# ver060_SignalAnalog.net
KiCad netlist of a schematic drawn in Altium Designer
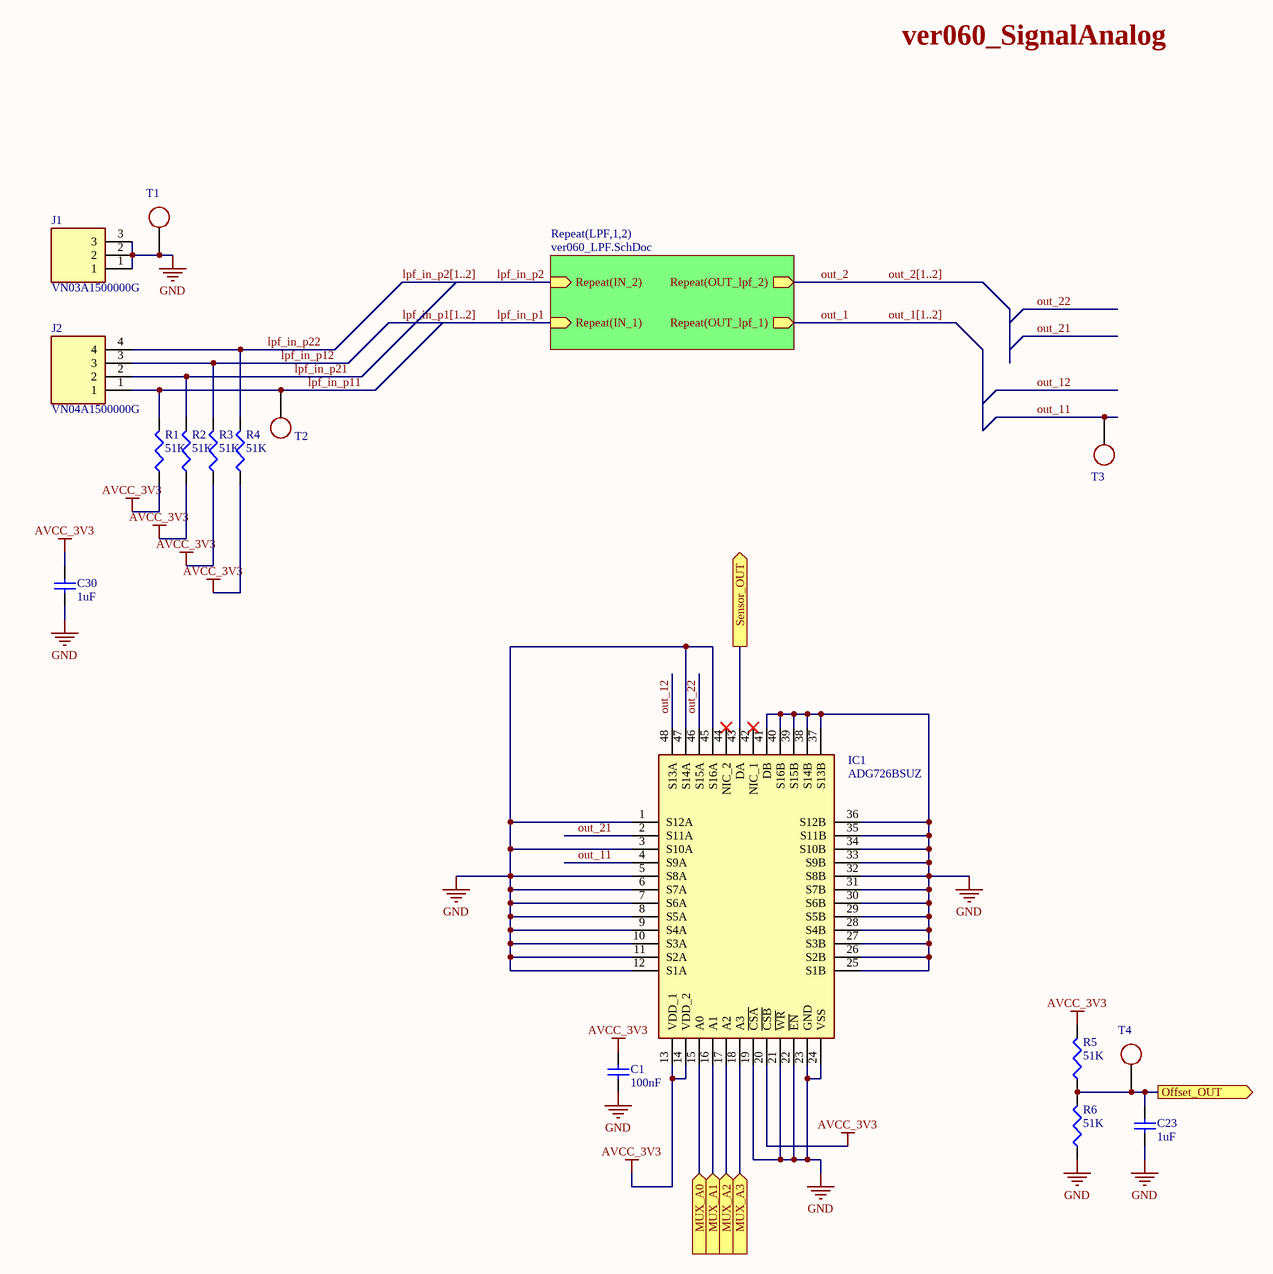
[diagram p0: ver060_SignalAnalog.SchDoc]

(export (version "E")
  (design (tool "Eeschema 10.0.6"))
  (components
    (comp (ref "C1")
      (value "100nF")
      (footprint "1608[0603]")
      (description "Capacitor (Semiconductor SIM Model)")
      (fields (field (name "Comment") "Cap Semi") (field (name "PUBLISHER") "Altium Limited"))
      (libsource (lib "Miscellaneous Devices") (part "Cap Semi"))
    )
    (comp (ref "C23")
      (value "1uF")
      (footprint "1608[0603]")
      (description "Capacitor (Semiconductor SIM Model)")
      (fields (field (name "Comment") "Cap Semi") (field (name "PUBLISHER") "Altium Limited"))
      (libsource (lib "Miscellaneous Devices") (part "Cap Semi"))
    )
    (comp (ref "C30")
      (value "1uF")
      (footprint "1608[0603]")
      (description "Capacitor (Semiconductor SIM Model)")
      (fields (field (name "Comment") "Cap Semi") (field (name "PUBLISHER") "Altium Limited"))
      (libsource (lib "Miscellaneous Devices") (part "Cap Semi"))
    )
    (comp (ref "IC1")
      (value "ADG726BSUZ")
      (footprint "nanowire:QFP50P900X900X120-48N")
      (description "Integrated Circuit")
      (fields (field (name "MOUSER PART NUMBER") "584-ADG726BSUZ"))
      (libsource (lib "*") (part "ADG726BSUZ"))
    )
    (comp (ref "J1")
      (value "VN03A1500000G")
      (footprint "nanowire:VN03A1500000G")
      (description "Connector")
      (fields (field (name "MOUSER PART NUMBER") "649-VN03A15000J0G"))
      (libsource (lib "*") (part "VN03A1500000G"))
    )
    (comp (ref "J2")
      (value "VN04A1500000G")
      (footprint "nanowire:VN04A1500000G")
      (description "Connector")
      (fields (field (name "MOUSER PART NUMBER") "649-VN04A15000J0G"))
      (libsource (lib "*") (part "VN04A1500000G"))
    )
    (comp (ref "R1")
      (value "51K")
      (footprint "J1-0603")
      (description "Resistor")
      (fields (field (name "Comment") "Res3") (field (name "PUBLISHER") "Altium Limited"))
      (libsource (lib "Miscellaneous Devices") (part "Res3"))
    )
    (comp (ref "R2")
      (value "51K")
      (footprint "J1-0603")
      (description "Resistor")
      (fields (field (name "Comment") "Res3") (field (name "PUBLISHER") "Altium Limited"))
      (libsource (lib "Miscellaneous Devices") (part "Res3"))
    )
    (comp (ref "R3")
      (value "51K")
      (footprint "J1-0603")
      (description "Resistor")
      (fields (field (name "Comment") "Res3") (field (name "PUBLISHER") "Altium Limited"))
      (libsource (lib "Miscellaneous Devices") (part "Res3"))
    )
    (comp (ref "R4")
      (value "51K")
      (footprint "J1-0603")
      (description "Resistor")
      (fields (field (name "Comment") "Res3") (field (name "PUBLISHER") "Altium Limited"))
      (libsource (lib "Miscellaneous Devices") (part "Res3"))
    )
    (comp (ref "R5")
      (value "51K")
      (footprint "J1-0603")
      (description "Resistor")
      (fields (field (name "Comment") "Res3") (field (name "PUBLISHER") "Altium Limited"))
      (libsource (lib "Miscellaneous Devices") (part "Res3"))
    )
    (comp (ref "R6")
      (value "51K")
      (footprint "J1-0603")
      (description "Resistor")
      (fields (field (name "Comment") "Res3") (field (name "PUBLISHER") "Altium Limited"))
      (libsource (lib "Miscellaneous Devices") (part "Res3"))
    )
    (comp (ref "T1")
      (value "TP_SMT")
      (footprint "TP_SMT_Round_0.6x0.6")
      (libsource (lib "nanowire") (part "TP_SMT"))
    )
    (comp (ref "T2")
      (value "TP_SMT")
      (footprint "TP_SMT_Round_0.6x0.6")
      (libsource (lib "nanowire") (part "TP_SMT"))
    )
    (comp (ref "T3")
      (value "TP_SMT")
      (footprint "TP_SMT_Round_0.6x0.6")
      (libsource (lib "nanowire") (part "TP_SMT"))
    )
    (comp (ref "T4")
      (value "TP_SMT")
      (footprint "TP_SMT_Round_0.6x0.6")
      (libsource (lib "nanowire") (part "TP_SMT"))
    )
  )
  (nets
    (net (code "1") (name "/MUX_A0") (class "Default")
      (node (ref "IC1") (pin "15") (pinfunction "A0_15") (pintype "passive"))
    )
    (net (code "2") (name "/MUX_A1") (class "Default")
      (node (ref "IC1") (pin "16") (pinfunction "A1_16") (pintype "passive"))
    )
    (net (code "3") (name "/MUX_A2") (class "Default")
      (node (ref "IC1") (pin "17") (pinfunction "A2_17") (pintype "passive"))
    )
    (net (code "4") (name "/MUX_A3") (class "Default")
      (node (ref "IC1") (pin "18") (pinfunction "A3_18") (pintype "passive"))
    )
    (net (code "5") (name "/Offset_OUT") (class "Default")
      (node (ref "C23") (pin "2") (pinfunction "2_2") (pintype "passive"))
      (node (ref "R5") (pin "1") (pinfunction "1_1") (pintype "passive"))
      (node (ref "R6") (pin "2") (pinfunction "2_2") (pintype "passive"))
      (node (ref "T4") (pin "1") (pinfunction "1_1") (pintype "passive"))
    )
    (net (code "6") (name "/Sensor_OUT") (class "Default")
      (node (ref "IC1") (pin "43") (pinfunction "DA_43") (pintype "passive"))
    )
    (net (code "11") (name "/lpf_in_p11") (class "Default")
      (node (ref "J2") (pin "1") (pinfunction "1_1") (pintype "passive"))
      (node (ref "R1") (pin "2") (pinfunction "2_2") (pintype "passive"))
      (node (ref "T2") (pin "1") (pinfunction "1_1") (pintype "passive"))
    )
    (net (code "12") (name "/lpf_in_p12") (class "Default")
      (node (ref "J2") (pin "3") (pinfunction "3_3") (pintype "passive"))
      (node (ref "R3") (pin "2") (pinfunction "2_2") (pintype "passive"))
    )
    (net (code "13") (name "/lpf_in_p21") (class "Default")
      (node (ref "J2") (pin "2") (pinfunction "2_2") (pintype "passive"))
      (node (ref "R2") (pin "2") (pinfunction "2_2") (pintype "passive"))
    )
    (net (code "14") (name "/lpf_in_p22") (class "Default")
      (node (ref "J2") (pin "4") (pinfunction "4_4") (pintype "passive"))
      (node (ref "R4") (pin "2") (pinfunction "2_2") (pintype "passive"))
    )
    (net (code "19") (name "/out_11") (class "Default")
      (node (ref "IC1") (pin "4") (pinfunction "S9A_4") (pintype "passive"))
      (node (ref "T3") (pin "1") (pinfunction "1_1") (pintype "passive"))
    )
    (net (code "20") (name "/out_12") (class "Default")
      (node (ref "IC1") (pin "48") (pinfunction "S13A_48") (pintype "passive"))
    )
    (net (code "21") (name "/out_21") (class "Default")
      (node (ref "IC1") (pin "2") (pinfunction "S11A_2") (pintype "passive"))
    )
    (net (code "22") (name "/out_22") (class "Default")
      (node (ref "IC1") (pin "46") (pinfunction "S15A_46") (pintype "passive"))
    )
    (net (code "23") (name "AVCC_3V3") (class "Default")
      (node (ref "C1") (pin "2") (pinfunction "2_2") (pintype "passive"))
      (node (ref "C30") (pin "2") (pinfunction "2_2") (pintype "passive"))
      (node (ref "IC1") (pin "13") (pinfunction "VDD_1_13") (pintype "passive"))
      (node (ref "IC1") (pin "14") (pinfunction "VDD_2_14") (pintype "passive"))
      (node (ref "IC1") (pin "20") (pinfunction "~{CSB}_20") (pintype "passive"))
      (node (ref "R1") (pin "1") (pinfunction "1_1") (pintype "passive"))
      (node (ref "R2") (pin "1") (pinfunction "1_1") (pintype "passive"))
      (node (ref "R3") (pin "1") (pinfunction "1_1") (pintype "passive"))
      (node (ref "R4") (pin "1") (pinfunction "1_1") (pintype "passive"))
      (node (ref "R5") (pin "2") (pinfunction "2_2") (pintype "passive"))
    )
    (net (code "24") (name "GND") (class "Default")
      (node (ref "C1") (pin "1") (pinfunction "1_1") (pintype "passive"))
      (node (ref "C23") (pin "1") (pinfunction "1_1") (pintype "passive"))
      (node (ref "C30") (pin "1") (pinfunction "1_1") (pintype "passive"))
      (node (ref "IC1") (pin "1") (pinfunction "S12A_1") (pintype "passive"))
      (node (ref "IC1") (pin "10") (pinfunction "S3A_10") (pintype "passive"))
      (node (ref "IC1") (pin "11") (pinfunction "S2A_11") (pintype "passive"))
      (node (ref "IC1") (pin "12") (pinfunction "S1A_12") (pintype "passive"))
      (node (ref "IC1") (pin "19") (pinfunction "~{CSA}_19") (pintype "passive"))
      (node (ref "IC1") (pin "21") (pinfunction "~{WR}_21") (pintype "passive"))
      (node (ref "IC1") (pin "22") (pinfunction "~{EN}_22") (pintype "passive"))
      (node (ref "IC1") (pin "23") (pinfunction "GND_23") (pintype "passive"))
      (node (ref "IC1") (pin "24") (pinfunction "VSS_24") (pintype "passive"))
      (node (ref "IC1") (pin "25") (pinfunction "S1B_25") (pintype "passive"))
      (node (ref "IC1") (pin "26") (pinfunction "S2B_26") (pintype "passive"))
      (node (ref "IC1") (pin "27") (pinfunction "S3B_27") (pintype "passive"))
      (node (ref "IC1") (pin "28") (pinfunction "S4B_28") (pintype "passive"))
      (node (ref "IC1") (pin "29") (pinfunction "S5B_29") (pintype "passive"))
      (node (ref "IC1") (pin "3") (pinfunction "S10A_3") (pintype "passive"))
      (node (ref "IC1") (pin "30") (pinfunction "S6B_30") (pintype "passive"))
      (node (ref "IC1") (pin "31") (pinfunction "S7B_31") (pintype "passive"))
      (node (ref "IC1") (pin "32") (pinfunction "S8B_32") (pintype "passive"))
      (node (ref "IC1") (pin "33") (pinfunction "S9B_33") (pintype "passive"))
      (node (ref "IC1") (pin "34") (pinfunction "S10B_34") (pintype "passive"))
      (node (ref "IC1") (pin "35") (pinfunction "S11B_35") (pintype "passive"))
      (node (ref "IC1") (pin "36") (pinfunction "S12B_36") (pintype "passive"))
      (node (ref "IC1") (pin "37") (pinfunction "S13B_37") (pintype "passive"))
      (node (ref "IC1") (pin "38") (pinfunction "S14B_38") (pintype "passive"))
      (node (ref "IC1") (pin "39") (pinfunction "S15B_39") (pintype "passive"))
      (node (ref "IC1") (pin "40") (pinfunction "S16B_40") (pintype "passive"))
      (node (ref "IC1") (pin "41") (pinfunction "DB_41") (pintype "passive"))
      (node (ref "IC1") (pin "45") (pinfunction "S16A_45") (pintype "passive"))
      (node (ref "IC1") (pin "47") (pinfunction "S14A_47") (pintype "passive"))
      (node (ref "IC1") (pin "5") (pinfunction "S8A_5") (pintype "passive"))
      (node (ref "IC1") (pin "6") (pinfunction "S7A_6") (pintype "passive"))
      (node (ref "IC1") (pin "7") (pinfunction "S6A_7") (pintype "passive"))
      (node (ref "IC1") (pin "8") (pinfunction "S5A_8") (pintype "passive"))
      (node (ref "IC1") (pin "9") (pinfunction "S4A_9") (pintype "passive"))
      (node (ref "J1") (pin "1") (pinfunction "1_1") (pintype "passive"))
      (node (ref "J1") (pin "2") (pinfunction "2_2") (pintype "passive"))
      (node (ref "J1") (pin "3") (pinfunction "3_3") (pintype "passive"))
      (node (ref "R6") (pin "1") (pinfunction "1_1") (pintype "passive"))
      (node (ref "T1") (pin "1") (pinfunction "1_1") (pintype "passive"))
    )
    (net (code "25") (name "unconnected-(IC1-NIC_1-Pad42)") (class "Default")
      (node (ref "IC1") (pin "42") (pinfunction "NIC_1_42") (pintype "passive+no_connect"))
    )
    (net (code "26") (name "unconnected-(IC1-NIC_2-Pad44)") (class "Default")
      (node (ref "IC1") (pin "44") (pinfunction "NIC_2_44") (pintype "passive+no_connect"))
    )
  )
)
